# DirtyPWM.net
KiCad netlist of a schematic drawn in Altium Designer
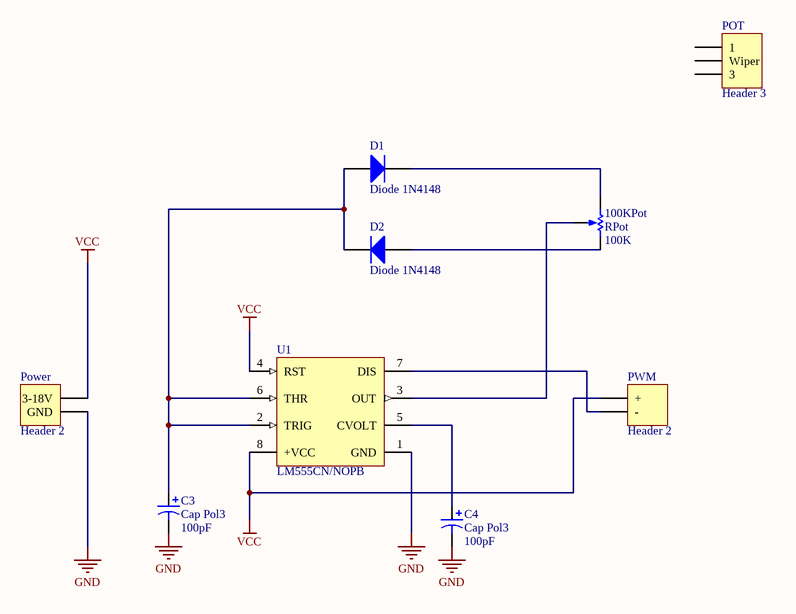
[diagram p0: DirtyPWM.SchDoc]

(export (version "E")
  (design (tool "Eeschema 10.0.6"))
  (components
    (comp (ref "100KPot")
      (value "RPot")
      (footprint "VR5")
      (description "Potentiometer")
      (fields (field (name "ALTIUM_VALUE") "100K") (field (name "PUBLISHER") "Altium Limited"))
      (libsource (lib "Miscellaneous Devices") (part "RPot"))
    )
    (comp (ref "C3")
      (value "Cap Pol3")
      (footprint "C0805")
      (description "Polarized Capacitor (Surface Mount)")
      (fields (field (name "ALTIUM_VALUE") "100pF") (field (name "PUBLISHER") "Altium Limited"))
      (libsource (lib "Miscellaneous Devices") (part "Cap Pol3"))
    )
    (comp (ref "C4")
      (value "Cap Pol3")
      (footprint "C0805")
      (description "Polarized Capacitor (Surface Mount)")
      (fields (field (name "ALTIUM_VALUE") "100pF") (field (name "PUBLISHER") "Altium Limited"))
      (libsource (lib "Miscellaneous Devices") (part "Cap Pol3"))
    )
    (comp (ref "D1")
      (value "Diode 1N4148")
      (footprint "DO-35")
      (description "High Conductance Fast Diode")
      (fields (field (name "PUBLISHER") "Altium Limited"))
      (libsource (lib "Miscellaneous Devices") (part "Diode 1N4148"))
    )
    (comp (ref "D2")
      (value "Diode 1N4148")
      (footprint "DO-35")
      (description "High Conductance Fast Diode")
      (fields (field (name "PUBLISHER") "Altium Limited"))
      (libsource (lib "Miscellaneous Devices") (part "Diode 1N4148"))
    )
    (comp (ref "POT")
      (value "Header 3")
      (footprint "HDR1X3")
      (description "Header, 3-Pin")
      (fields (field (name "PUBLISHER") "Altium Limited"))
      (libsource (lib "Miscellaneous Connectors") (part "Header 3"))
    )
    (comp (ref "Power")
      (value "Header 2")
      (footprint "HDR1X2")
      (description "Header, 2-Pin")
      (fields (field (name "PUBLISHER") "Altium Limited"))
      (libsource (lib "") (part "Header 2_1"))
    )
    (comp (ref "PWM")
      (value "Header 2")
      (footprint "HDR1X2")
      (description "Header, 2-Pin")
      (fields (field (name "PUBLISHER") "Altium Limited"))
      (libsource (lib "Miscellaneous Connectors") (part "Header 2"))
    )
    (comp (ref "U1")
      (value "LM555CN/NOPB")
      (footprint "N08E")
      (description "Timer, 8-pin MDIP, Pb-Free")
      (fields (field (name "MANUFACTURER") "National Semiconductor"))
      (libsource (lib "Altium Content Vault") (part "AN-TIMER-LM555-8"))
    )
  )
  (nets
    (net (code "1") (name "GND") (class "Default")
      (node (ref "C3") (pin "2") (pinfunction "2_2") (pintype "passive"))
      (node (ref "C4") (pin "2") (pinfunction "2_2") (pintype "passive"))
      (node (ref "Power") (pin "2") (pinfunction "GND_2") (pintype "passive"))
      (node (ref "U1") (pin "1") (pinfunction "GND_1") (pintype "power_in"))
    )
    (net (code "2") (name "Net-(100KPot-BOT)") (class "Default")
      (node (ref "100KPot") (pin "2") (pinfunction "BOT_2") (pintype "passive"))
      (node (ref "D2") (pin "1") (pinfunction "A_1") (pintype "passive"))
    )
    (net (code "3") (name "Net-(100KPot-TAP)") (class "Default")
      (node (ref "100KPot") (pin "3") (pinfunction "TAP_3") (pintype "passive"))
      (node (ref "U1") (pin "3") (pinfunction "OUT_3") (pintype "output"))
    )
    (net (code "4") (name "Net-(100KPot-TOP)") (class "Default")
      (node (ref "100KPot") (pin "1") (pinfunction "TOP_1") (pintype "passive"))
      (node (ref "D1") (pin "2") (pinfunction "K_2") (pintype "passive"))
    )
    (net (code "5") (name "Net-(D1-A)") (class "Default")
      (node (ref "C3") (pin "1") (pinfunction "1_1") (pintype "passive"))
      (node (ref "D1") (pin "1") (pinfunction "A_1") (pintype "passive"))
      (node (ref "D2") (pin "2") (pinfunction "K_2") (pintype "passive"))
      (node (ref "U1") (pin "2") (pinfunction "TRIG_2") (pintype "input"))
      (node (ref "U1") (pin "6") (pinfunction "THR_6") (pintype "input"))
    )
    (net (code "6") (name "Net-(PWM--)") (class "Default")
      (node (ref "PWM") (pin "2") (pinfunction "-_2") (pintype "passive"))
      (node (ref "U1") (pin "7") (pinfunction "DIS_7") (pintype "open_collector"))
    )
    (net (code "7") (name "Net-(U1-CVOLT)") (class "Default")
      (node (ref "C4") (pin "1") (pinfunction "1_1") (pintype "passive"))
      (node (ref "U1") (pin "5") (pinfunction "CVOLT_5") (pintype "passive"))
    )
    (net (code "8") (name "VCC") (class "Default")
      (node (ref "PWM") (pin "1") (pinfunction "+_1") (pintype "passive"))
      (node (ref "Power") (pin "1") (pinfunction "3-18V_1") (pintype "passive"))
      (node (ref "U1") (pin "4") (pinfunction "RST_4") (pintype "input"))
      (node (ref "U1") (pin "8") (pinfunction "+VCC_8") (pintype "power_in"))
    )
    (net (code "9") (name "unconnected-(POT-Pad1)") (class "Default")
      (node (ref "POT") (pin "1") (pinfunction "1_1") (pintype "passive"))
    )
    (net (code "10") (name "unconnected-(POT-Pad3)") (class "Default")
      (node (ref "POT") (pin "3") (pinfunction "3_3") (pintype "passive"))
    )
    (net (code "11") (name "unconnected-(POT-Wiper-Pad2)") (class "Default")
      (node (ref "POT") (pin "2") (pinfunction "Wiper_2") (pintype "passive"))
    )
  )
)
